# EIB_A79024-001.net
KiCad netlist of a schematic drawn in EAGLE
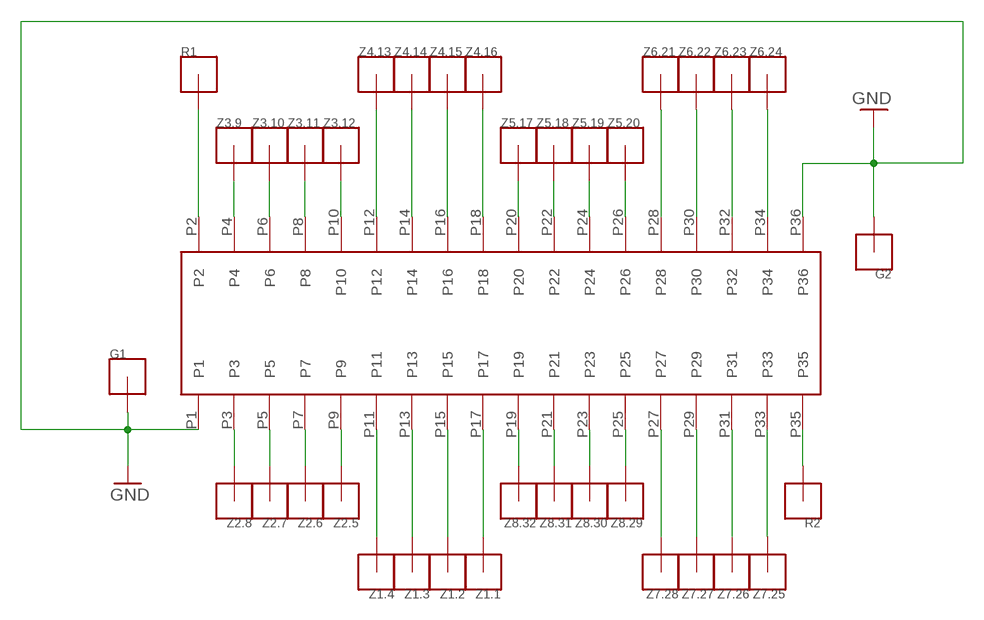
[diagram p0: schematic, sheet 1]

(export (version "E")
  (design (tool "Eeschema 10.0.6"))
  (components
    (comp (ref "A79024")
      (value "OMNETICS")
      (footprint "eagle-import:A79024")
      (libsource (lib "eagle-import") (part "OMNETICS"))
    )
    (comp (ref "G1")
      (value "S_P_HOLE")
      (footprint "eagle-import:S_P_HOLE")
      (libsource (lib "eagle-import") (part "S_P_HOLE"))
    )
    (comp (ref "G2")
      (value "S_P_HOLE")
      (footprint "eagle-import:S_P_HOLE")
      (libsource (lib "eagle-import") (part "S_P_HOLE"))
    )
    (comp (ref "R1")
      (value "S_P_HOLE")
      (footprint "eagle-import:S_P_HOLE")
      (libsource (lib "eagle-import") (part "S_P_HOLE"))
    )
    (comp (ref "R2")
      (value "S_P_HOLE")
      (footprint "eagle-import:S_P_HOLE")
      (libsource (lib "eagle-import") (part "S_P_HOLE"))
    )
    (comp (ref "Z1.1")
      (value "S_P_HOLE")
      (footprint "eagle-import:S_P_HOLE")
      (libsource (lib "eagle-import") (part "S_P_HOLE"))
    )
    (comp (ref "Z1.2")
      (value "S_P_HOLE")
      (footprint "eagle-import:S_P_HOLE")
      (libsource (lib "eagle-import") (part "S_P_HOLE"))
    )
    (comp (ref "Z1.3")
      (value "S_P_HOLE")
      (footprint "eagle-import:S_P_HOLE")
      (libsource (lib "eagle-import") (part "S_P_HOLE"))
    )
    (comp (ref "Z1.4")
      (value "S_P_HOLE")
      (footprint "eagle-import:S_P_HOLE")
      (libsource (lib "eagle-import") (part "S_P_HOLE"))
    )
    (comp (ref "Z2.5")
      (value "S_P_HOLE")
      (footprint "eagle-import:S_P_HOLE")
      (libsource (lib "eagle-import") (part "S_P_HOLE"))
    )
    (comp (ref "Z2.6")
      (value "S_P_HOLE")
      (footprint "eagle-import:S_P_HOLE")
      (libsource (lib "eagle-import") (part "S_P_HOLE"))
    )
    (comp (ref "Z2.7")
      (value "S_P_HOLE")
      (footprint "eagle-import:S_P_HOLE")
      (libsource (lib "eagle-import") (part "S_P_HOLE"))
    )
    (comp (ref "Z2.8")
      (value "S_P_HOLE")
      (footprint "eagle-import:S_P_HOLE")
      (libsource (lib "eagle-import") (part "S_P_HOLE"))
    )
    (comp (ref "Z3.9")
      (value "S_P_HOLE")
      (footprint "eagle-import:S_P_HOLE")
      (libsource (lib "eagle-import") (part "S_P_HOLE"))
    )
    (comp (ref "Z3.10")
      (value "S_P_HOLE")
      (footprint "eagle-import:S_P_HOLE")
      (libsource (lib "eagle-import") (part "S_P_HOLE"))
    )
    (comp (ref "Z3.11")
      (value "S_P_HOLE")
      (footprint "eagle-import:S_P_HOLE")
      (libsource (lib "eagle-import") (part "S_P_HOLE"))
    )
    (comp (ref "Z3.12")
      (value "S_P_HOLE")
      (footprint "eagle-import:S_P_HOLE")
      (libsource (lib "eagle-import") (part "S_P_HOLE"))
    )
    (comp (ref "Z4.13")
      (value "S_P_HOLE")
      (footprint "eagle-import:S_P_HOLE")
      (libsource (lib "eagle-import") (part "S_P_HOLE"))
    )
    (comp (ref "Z4.14")
      (value "S_P_HOLE")
      (footprint "eagle-import:S_P_HOLE")
      (libsource (lib "eagle-import") (part "S_P_HOLE"))
    )
    (comp (ref "Z4.15")
      (value "S_P_HOLE")
      (footprint "eagle-import:S_P_HOLE")
      (libsource (lib "eagle-import") (part "S_P_HOLE"))
    )
    (comp (ref "Z4.16")
      (value "S_P_HOLE")
      (footprint "eagle-import:S_P_HOLE")
      (libsource (lib "eagle-import") (part "S_P_HOLE"))
    )
    (comp (ref "Z5.17")
      (value "S_P_HOLE")
      (footprint "eagle-import:S_P_HOLE")
      (libsource (lib "eagle-import") (part "S_P_HOLE"))
    )
    (comp (ref "Z5.18")
      (value "S_P_HOLE")
      (footprint "eagle-import:S_P_HOLE")
      (libsource (lib "eagle-import") (part "S_P_HOLE"))
    )
    (comp (ref "Z5.19")
      (value "S_P_HOLE")
      (footprint "eagle-import:S_P_HOLE")
      (libsource (lib "eagle-import") (part "S_P_HOLE"))
    )
    (comp (ref "Z5.20")
      (value "S_P_HOLE")
      (footprint "eagle-import:S_P_HOLE")
      (libsource (lib "eagle-import") (part "S_P_HOLE"))
    )
    (comp (ref "Z6.21")
      (value "S_P_HOLE")
      (footprint "eagle-import:S_P_HOLE")
      (libsource (lib "eagle-import") (part "S_P_HOLE"))
    )
    (comp (ref "Z6.22")
      (value "S_P_HOLE")
      (footprint "eagle-import:S_P_HOLE")
      (libsource (lib "eagle-import") (part "S_P_HOLE"))
    )
    (comp (ref "Z6.23")
      (value "S_P_HOLE")
      (footprint "eagle-import:S_P_HOLE")
      (libsource (lib "eagle-import") (part "S_P_HOLE"))
    )
    (comp (ref "Z6.24")
      (value "S_P_HOLE")
      (footprint "eagle-import:S_P_HOLE")
      (libsource (lib "eagle-import") (part "S_P_HOLE"))
    )
    (comp (ref "Z7.25")
      (value "S_P_HOLE")
      (footprint "eagle-import:S_P_HOLE")
      (libsource (lib "eagle-import") (part "S_P_HOLE"))
    )
    (comp (ref "Z7.26")
      (value "S_P_HOLE")
      (footprint "eagle-import:S_P_HOLE")
      (libsource (lib "eagle-import") (part "S_P_HOLE"))
    )
    (comp (ref "Z7.27")
      (value "S_P_HOLE")
      (footprint "eagle-import:S_P_HOLE")
      (libsource (lib "eagle-import") (part "S_P_HOLE"))
    )
    (comp (ref "Z7.28")
      (value "S_P_HOLE")
      (footprint "eagle-import:S_P_HOLE")
      (libsource (lib "eagle-import") (part "S_P_HOLE"))
    )
    (comp (ref "Z8.29")
      (value "S_P_HOLE")
      (footprint "eagle-import:S_P_HOLE")
      (libsource (lib "eagle-import") (part "S_P_HOLE"))
    )
    (comp (ref "Z8.30")
      (value "S_P_HOLE")
      (footprint "eagle-import:S_P_HOLE")
      (libsource (lib "eagle-import") (part "S_P_HOLE"))
    )
    (comp (ref "Z8.31")
      (value "S_P_HOLE")
      (footprint "eagle-import:S_P_HOLE")
      (libsource (lib "eagle-import") (part "S_P_HOLE"))
    )
    (comp (ref "Z8.32")
      (value "S_P_HOLE")
      (footprint "eagle-import:S_P_HOLE")
      (libsource (lib "eagle-import") (part "S_P_HOLE"))
    )
  )
  (nets
    (net (code "1") (name "GND") (class "Default")
      (node (ref "A79024") (pin "P1") (pinfunction "P1_P1") (pintype "bidirectional"))
      (node (ref "A79024") (pin "P36") (pinfunction "P36_P36") (pintype "bidirectional"))
      (node (ref "G1") (pin "P1") (pinfunction "P1_P1") (pintype "bidirectional"))
      (node (ref "G2") (pin "P1") (pinfunction "P1_P1") (pintype "bidirectional"))
    )
    (net (code "2") (name "Net-(A79024-PadP2)") (class "Default")
      (node (ref "A79024") (pin "P2") (pinfunction "P2_P2") (pintype "bidirectional"))
      (node (ref "R1") (pin "P1") (pinfunction "P1_P1") (pintype "bidirectional"))
    )
    (net (code "3") (name "Net-(A79024-PadP3)") (class "Default")
      (node (ref "A79024") (pin "P3") (pinfunction "P3_P3") (pintype "bidirectional"))
      (node (ref "Z2.8") (pin "P1") (pinfunction "P1_P1") (pintype "bidirectional"))
    )
    (net (code "4") (name "Net-(A79024-PadP4)") (class "Default")
      (node (ref "A79024") (pin "P4") (pinfunction "P4_P4") (pintype "bidirectional"))
      (node (ref "Z3.9") (pin "P1") (pinfunction "P1_P1") (pintype "bidirectional"))
    )
    (net (code "5") (name "Net-(A79024-PadP5)") (class "Default")
      (node (ref "A79024") (pin "P5") (pinfunction "P5_P5") (pintype "bidirectional"))
      (node (ref "Z2.7") (pin "P1") (pinfunction "P1_P1") (pintype "bidirectional"))
    )
    (net (code "6") (name "Net-(A79024-PadP6)") (class "Default")
      (node (ref "A79024") (pin "P6") (pinfunction "P6_P6") (pintype "bidirectional"))
      (node (ref "Z3.10") (pin "P1") (pinfunction "P1_P1") (pintype "bidirectional"))
    )
    (net (code "7") (name "Net-(A79024-PadP7)") (class "Default")
      (node (ref "A79024") (pin "P7") (pinfunction "P7_P7") (pintype "bidirectional"))
      (node (ref "Z2.6") (pin "P1") (pinfunction "P1_P1") (pintype "bidirectional"))
    )
    (net (code "8") (name "Net-(A79024-PadP8)") (class "Default")
      (node (ref "A79024") (pin "P8") (pinfunction "P8_P8") (pintype "bidirectional"))
      (node (ref "Z3.11") (pin "P1") (pinfunction "P1_P1") (pintype "bidirectional"))
    )
    (net (code "9") (name "Net-(A79024-PadP9)") (class "Default")
      (node (ref "A79024") (pin "P9") (pinfunction "P9_P9") (pintype "bidirectional"))
      (node (ref "Z2.5") (pin "P1") (pinfunction "P1_P1") (pintype "bidirectional"))
    )
    (net (code "10") (name "Net-(A79024-PadP10)") (class "Default")
      (node (ref "A79024") (pin "P10") (pinfunction "P10_P10") (pintype "bidirectional"))
      (node (ref "Z3.12") (pin "P1") (pinfunction "P1_P1") (pintype "bidirectional"))
    )
    (net (code "11") (name "Net-(A79024-PadP11)") (class "Default")
      (node (ref "A79024") (pin "P11") (pinfunction "P11_P11") (pintype "bidirectional"))
      (node (ref "Z1.4") (pin "P1") (pinfunction "P1_P1") (pintype "bidirectional"))
    )
    (net (code "12") (name "Net-(A79024-PadP12)") (class "Default")
      (node (ref "A79024") (pin "P12") (pinfunction "P12_P12") (pintype "bidirectional"))
      (node (ref "Z4.13") (pin "P1") (pinfunction "P1_P1") (pintype "bidirectional"))
    )
    (net (code "13") (name "Net-(A79024-PadP13)") (class "Default")
      (node (ref "A79024") (pin "P13") (pinfunction "P13_P13") (pintype "bidirectional"))
      (node (ref "Z1.3") (pin "P1") (pinfunction "P1_P1") (pintype "bidirectional"))
    )
    (net (code "14") (name "Net-(A79024-PadP14)") (class "Default")
      (node (ref "A79024") (pin "P14") (pinfunction "P14_P14") (pintype "bidirectional"))
      (node (ref "Z4.14") (pin "P1") (pinfunction "P1_P1") (pintype "bidirectional"))
    )
    (net (code "15") (name "Net-(A79024-PadP15)") (class "Default")
      (node (ref "A79024") (pin "P15") (pinfunction "P15_P15") (pintype "bidirectional"))
      (node (ref "Z1.2") (pin "P1") (pinfunction "P1_P1") (pintype "bidirectional"))
    )
    (net (code "16") (name "Net-(A79024-PadP16)") (class "Default")
      (node (ref "A79024") (pin "P16") (pinfunction "P16_P16") (pintype "bidirectional"))
      (node (ref "Z4.15") (pin "P1") (pinfunction "P1_P1") (pintype "bidirectional"))
    )
    (net (code "17") (name "Net-(A79024-PadP17)") (class "Default")
      (node (ref "A79024") (pin "P17") (pinfunction "P17_P17") (pintype "bidirectional"))
      (node (ref "Z1.1") (pin "P1") (pinfunction "P1_P1") (pintype "bidirectional"))
    )
    (net (code "18") (name "Net-(A79024-PadP18)") (class "Default")
      (node (ref "A79024") (pin "P18") (pinfunction "P18_P18") (pintype "bidirectional"))
      (node (ref "Z4.16") (pin "P1") (pinfunction "P1_P1") (pintype "bidirectional"))
    )
    (net (code "19") (name "Net-(A79024-PadP19)") (class "Default")
      (node (ref "A79024") (pin "P19") (pinfunction "P19_P19") (pintype "bidirectional"))
      (node (ref "Z8.32") (pin "P1") (pinfunction "P1_P1") (pintype "bidirectional"))
    )
    (net (code "20") (name "Net-(A79024-PadP20)") (class "Default")
      (node (ref "A79024") (pin "P20") (pinfunction "P20_P20") (pintype "bidirectional"))
      (node (ref "Z5.17") (pin "P1") (pinfunction "P1_P1") (pintype "bidirectional"))
    )
    (net (code "21") (name "Net-(A79024-PadP21)") (class "Default")
      (node (ref "A79024") (pin "P21") (pinfunction "P21_P21") (pintype "bidirectional"))
      (node (ref "Z8.31") (pin "P1") (pinfunction "P1_P1") (pintype "bidirectional"))
    )
    (net (code "22") (name "Net-(A79024-PadP22)") (class "Default")
      (node (ref "A79024") (pin "P22") (pinfunction "P22_P22") (pintype "bidirectional"))
      (node (ref "Z5.18") (pin "P1") (pinfunction "P1_P1") (pintype "bidirectional"))
    )
    (net (code "23") (name "Net-(A79024-PadP23)") (class "Default")
      (node (ref "A79024") (pin "P23") (pinfunction "P23_P23") (pintype "bidirectional"))
      (node (ref "Z8.30") (pin "P1") (pinfunction "P1_P1") (pintype "bidirectional"))
    )
    (net (code "24") (name "Net-(A79024-PadP24)") (class "Default")
      (node (ref "A79024") (pin "P24") (pinfunction "P24_P24") (pintype "bidirectional"))
      (node (ref "Z5.19") (pin "P1") (pinfunction "P1_P1") (pintype "bidirectional"))
    )
    (net (code "25") (name "Net-(A79024-PadP25)") (class "Default")
      (node (ref "A79024") (pin "P25") (pinfunction "P25_P25") (pintype "bidirectional"))
      (node (ref "Z8.29") (pin "P1") (pinfunction "P1_P1") (pintype "bidirectional"))
    )
    (net (code "26") (name "Net-(A79024-PadP26)") (class "Default")
      (node (ref "A79024") (pin "P26") (pinfunction "P26_P26") (pintype "bidirectional"))
      (node (ref "Z5.20") (pin "P1") (pinfunction "P1_P1") (pintype "bidirectional"))
    )
    (net (code "27") (name "Net-(A79024-PadP27)") (class "Default")
      (node (ref "A79024") (pin "P27") (pinfunction "P27_P27") (pintype "bidirectional"))
      (node (ref "Z7.28") (pin "P1") (pinfunction "P1_P1") (pintype "bidirectional"))
    )
    (net (code "28") (name "Net-(A79024-PadP28)") (class "Default")
      (node (ref "A79024") (pin "P28") (pinfunction "P28_P28") (pintype "bidirectional"))
      (node (ref "Z6.21") (pin "P1") (pinfunction "P1_P1") (pintype "bidirectional"))
    )
    (net (code "29") (name "Net-(A79024-PadP29)") (class "Default")
      (node (ref "A79024") (pin "P29") (pinfunction "P29_P29") (pintype "bidirectional"))
      (node (ref "Z7.27") (pin "P1") (pinfunction "P1_P1") (pintype "bidirectional"))
    )
    (net (code "30") (name "Net-(A79024-PadP30)") (class "Default")
      (node (ref "A79024") (pin "P30") (pinfunction "P30_P30") (pintype "bidirectional"))
      (node (ref "Z6.22") (pin "P1") (pinfunction "P1_P1") (pintype "bidirectional"))
    )
    (net (code "31") (name "Net-(A79024-PadP31)") (class "Default")
      (node (ref "A79024") (pin "P31") (pinfunction "P31_P31") (pintype "bidirectional"))
      (node (ref "Z7.26") (pin "P1") (pinfunction "P1_P1") (pintype "bidirectional"))
    )
    (net (code "32") (name "Net-(A79024-PadP32)") (class "Default")
      (node (ref "A79024") (pin "P32") (pinfunction "P32_P32") (pintype "bidirectional"))
      (node (ref "Z6.23") (pin "P1") (pinfunction "P1_P1") (pintype "bidirectional"))
    )
    (net (code "33") (name "Net-(A79024-PadP33)") (class "Default")
      (node (ref "A79024") (pin "P33") (pinfunction "P33_P33") (pintype "bidirectional"))
      (node (ref "Z7.25") (pin "P1") (pinfunction "P1_P1") (pintype "bidirectional"))
    )
    (net (code "34") (name "Net-(A79024-PadP34)") (class "Default")
      (node (ref "A79024") (pin "P34") (pinfunction "P34_P34") (pintype "bidirectional"))
      (node (ref "Z6.24") (pin "P1") (pinfunction "P1_P1") (pintype "bidirectional"))
    )
    (net (code "35") (name "Net-(A79024-PadP35)") (class "Default")
      (node (ref "A79024") (pin "P35") (pinfunction "P35_P35") (pintype "bidirectional"))
      (node (ref "R2") (pin "P1") (pinfunction "P1_P1") (pintype "bidirectional"))
    )
  )
)
